# mcu_v052.net
KiCad netlist of a schematic drawn in EAGLE
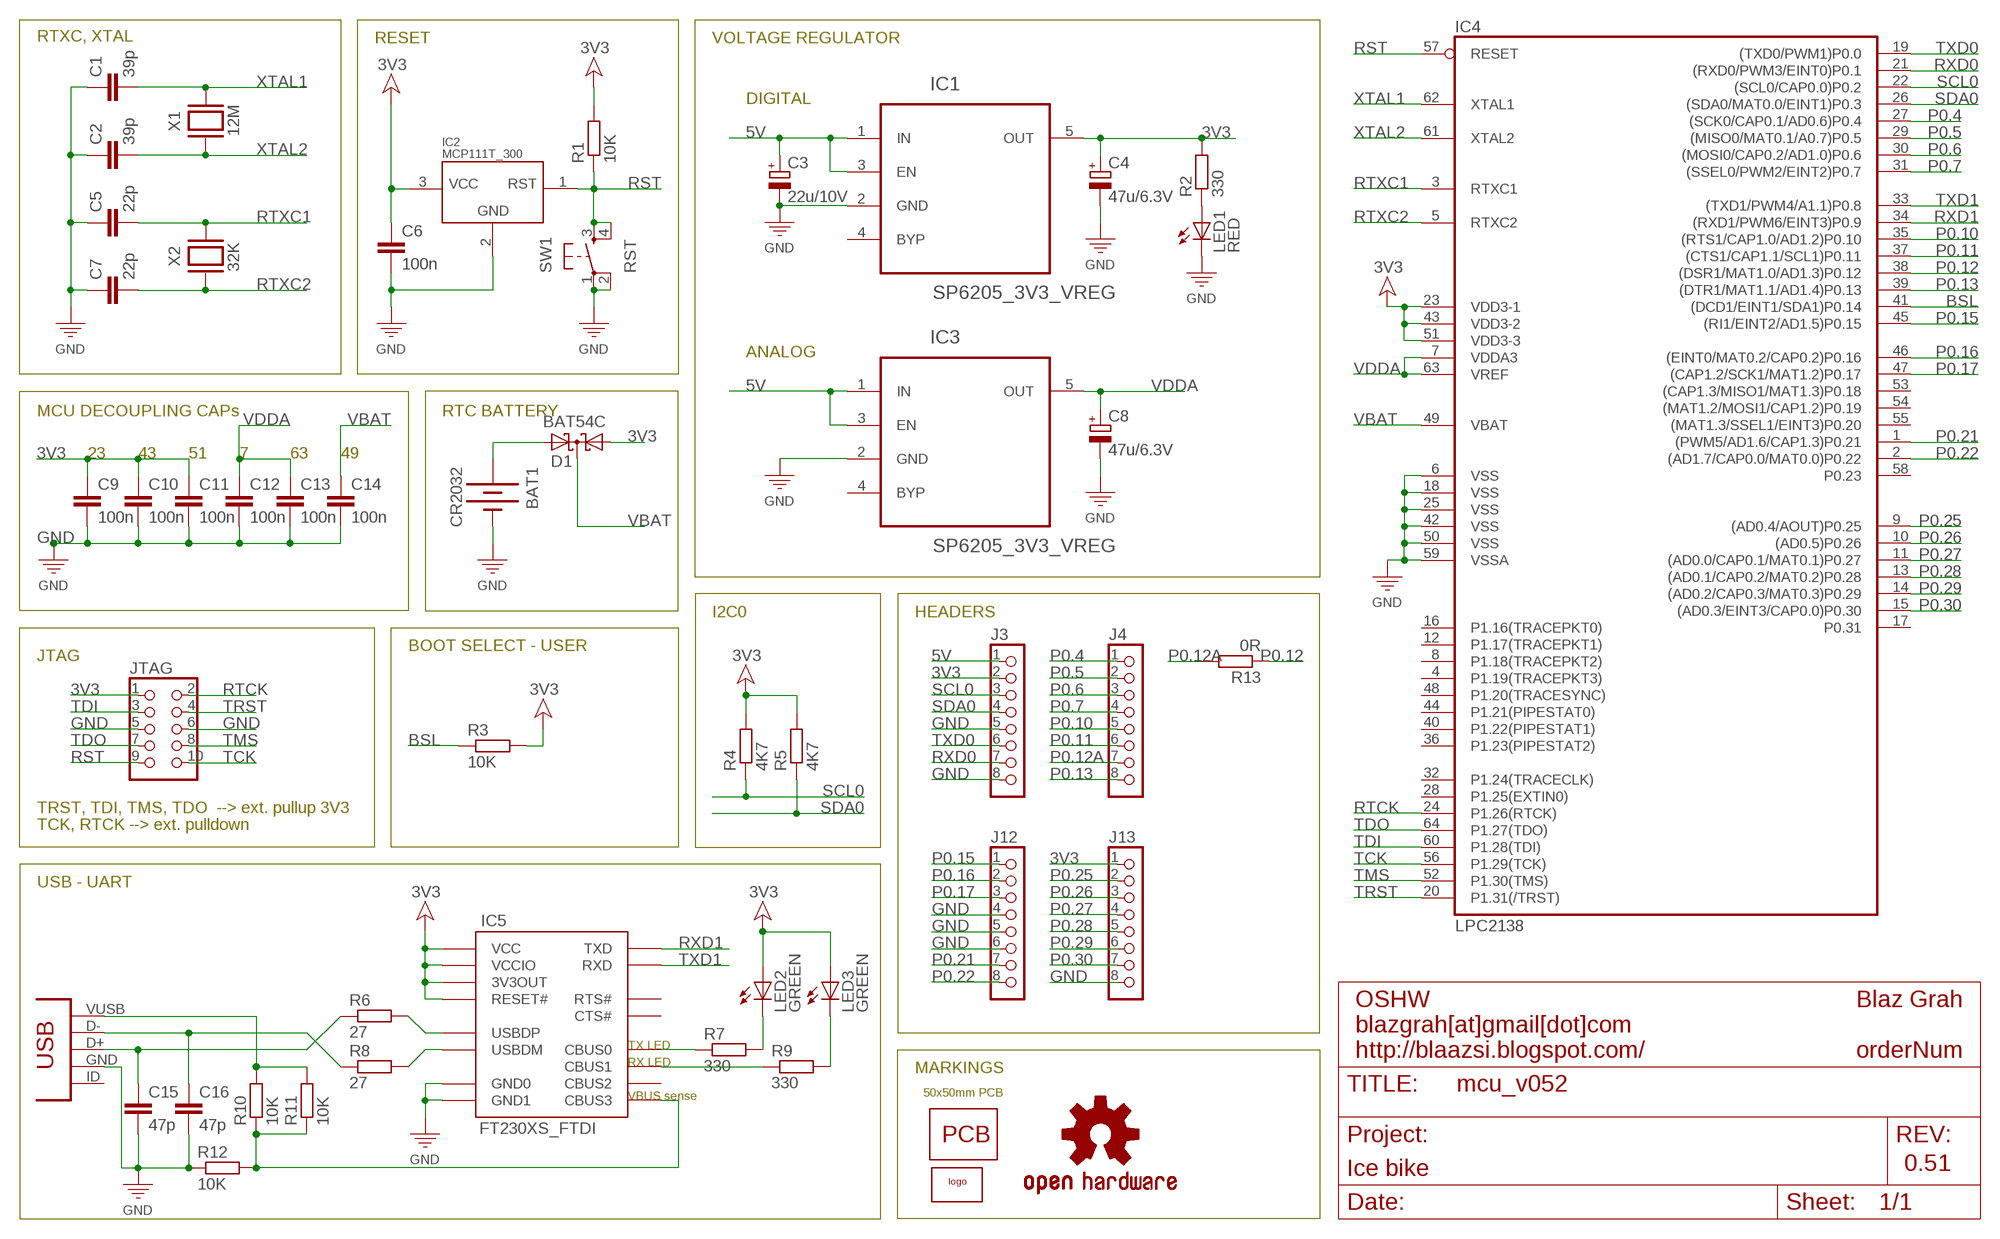
[diagram p0: schematic, sheet 1]

(export (version "E")
  (design (tool "Eeschema 10.0.6"))
  (components
    (comp (ref "BAT1")
      (value "CR2032")
      (footprint "eagle-import:BATTERY_20MM_SMD")
      (libsource (lib "eagle-import") (part "BATTERY20MM"))
    )
    (comp (ref "C1")
      (value "39p")
      (footprint "eagle-import:C0603")
      (libsource (lib "eagle-import") (part "C-EUC0603"))
    )
    (comp (ref "C2")
      (value "39p")
      (footprint "eagle-import:C0603")
      (libsource (lib "eagle-import") (part "C-EUC0603"))
    )
    (comp (ref "C3")
      (value "22u/10V")
      (footprint "eagle-import:SMC_B")
      (libsource (lib "eagle-import") (part "CAPACITOR_POL-SMC_B"))
    )
    (comp (ref "C4")
      (value "47u/6.3V")
      (footprint "eagle-import:SMC_B")
      (libsource (lib "eagle-import") (part "CAPACITOR_POL-SMC_B"))
    )
    (comp (ref "C5")
      (value "22p")
      (footprint "eagle-import:C0603")
      (libsource (lib "eagle-import") (part "C-EUC0603"))
    )
    (comp (ref "C6")
      (value "100n")
      (footprint "eagle-import:C0603")
      (libsource (lib "eagle-import") (part "C-EUC0603"))
    )
    (comp (ref "C7")
      (value "22p")
      (footprint "eagle-import:C0603")
      (libsource (lib "eagle-import") (part "C-EUC0603"))
    )
    (comp (ref "C8")
      (value "47u/6.3V")
      (footprint "eagle-import:SMC_B")
      (libsource (lib "eagle-import") (part "CAPACITOR_POL-SMC_B"))
    )
    (comp (ref "C9")
      (value "100n")
      (footprint "eagle-import:C0603")
      (libsource (lib "eagle-import") (part "C-EUC0603"))
    )
    (comp (ref "C10")
      (value "100n")
      (footprint "eagle-import:C0603")
      (libsource (lib "eagle-import") (part "C-EUC0603"))
    )
    (comp (ref "C11")
      (value "100n")
      (footprint "eagle-import:C0603")
      (libsource (lib "eagle-import") (part "C-EUC0603"))
    )
    (comp (ref "C12")
      (value "100n")
      (footprint "eagle-import:C0603")
      (libsource (lib "eagle-import") (part "C-EUC0603"))
    )
    (comp (ref "C13")
      (value "100n")
      (footprint "eagle-import:C0603")
      (libsource (lib "eagle-import") (part "C-EUC0603"))
    )
    (comp (ref "C14")
      (value "100n")
      (footprint "eagle-import:C0603")
      (libsource (lib "eagle-import") (part "C-EUC0603"))
    )
    (comp (ref "C15")
      (value "47p")
      (footprint "eagle-import:C0603")
      (libsource (lib "eagle-import") (part "C-EUC0603"))
    )
    (comp (ref "C16")
      (value "47p")
      (footprint "eagle-import:C0603")
      (libsource (lib "eagle-import") (part "C-EUC0603"))
    )
    (comp (ref "D1")
      (value "BAT54C")
      (footprint "eagle-import:SOT23")
      (libsource (lib "eagle-import") (part "BAT54C"))
    )
    (comp (ref "DOC")
      (value "FRAME_DINA4_L")
      (footprint "eagle-import:DP_LOGO")
      (fields
        (field (name "AUTHOR") "Blaz Grah")
        (field (name "DATE") "23.4.2012")
        (field (name "LICENSE") "OSHW")
        (field (name "PROJECT") "Ice bike")
        (field (name "REV") "0.51")
        (field (name "URL1") "blazgrah[at]gmail[dot]com")
        (field (name "URL2") "http://blaazsi.blogspot.com/")
      )
      (libsource (lib "eagle-import") (part "FRAME_DINA4_L"))
    )
    (comp (ref "IC1")
      (value "SP6205_3V3_VREG")
      (footprint "eagle-import:SOT23-5")
      (libsource (lib "eagle-import") (part "SP6205_3V3_VREG"))
    )
    (comp (ref "IC2")
      (value "MCP111T_300")
      (footprint "eagle-import:SOT23")
      (libsource (lib "eagle-import") (part "MCP111T_300"))
    )
    (comp (ref "IC3")
      (value "SP6205_3V3_VREG")
      (footprint "eagle-import:SOT23-5")
      (libsource (lib "eagle-import") (part "SP6205_3V3_VREG"))
    )
    (comp (ref "IC4")
      (value "LPC2138")
      (footprint "eagle-import:LQFP64")
      (libsource (lib "eagle-import") (part "LCP2138_LQFP64"))
    )
    (comp (ref "IC5")
      (value "FT230XS_FTDI")
      (footprint "eagle-import:SSOP16")
      (libsource (lib "eagle-import") (part "FT230XS_FTDI"))
    )
    (comp (ref "J3")
      (value "CON_HEADER_1X08-PTH")
      (footprint "eagle-import:M1X8")
      (libsource (lib "eagle-import") (part "CON_HEADER_1X08-PTH"))
    )
    (comp (ref "J4")
      (value "CON_HEADER_1X08-PTH")
      (footprint "eagle-import:M1X8")
      (libsource (lib "eagle-import") (part "CON_HEADER_1X08-PTH"))
    )
    (comp (ref "J12")
      (value "CON_HEADER_1X08-PTH")
      (footprint "eagle-import:M1X8")
      (libsource (lib "eagle-import") (part "CON_HEADER_1X08-PTH"))
    )
    (comp (ref "J13")
      (value "CON_HEADER_1X08-PTH")
      (footprint "eagle-import:M1X8")
      (libsource (lib "eagle-import") (part "CON_HEADER_1X08-PTH"))
    )
    (comp (ref "JTAG")
      (value "CON_HEADER_2X05-PTH+SHROUDED_A")
      (footprint "eagle-import:PINSHRD_PTH_2X05")
      (libsource (lib "eagle-import") (part "CON_HEADER_2X05-PTH+SHROUDED_A"))
    )
    (comp (ref "LED1")
      (value "RED")
      (footprint "eagle-import:LED0805")
      (libsource (lib "eagle-import") (part "LED0805"))
    )
    (comp (ref "LED2")
      (value "GREEN")
      (footprint "eagle-import:LED0805")
      (libsource (lib "eagle-import") (part "LED0805"))
    )
    (comp (ref "LED3")
      (value "GREEN")
      (footprint "eagle-import:LED0805")
      (libsource (lib "eagle-import") (part "LED0805"))
    )
    (comp (ref "LOGO1")
      (value "OSHW-LOGOS")
      (footprint "eagle-import:OSHW-LOGO-S")
      (libsource (lib "eagle-import") (part "OSHW-LOGOS"))
    )
    (comp (ref "PCB1")
      (value "PCB")
      (footprint "eagle-import:PCB_50X50")
      (libsource (lib "eagle-import") (part "PCB"))
    )
    (comp (ref "R1")
      (value "10K")
      (footprint "eagle-import:R0603")
      (libsource (lib "eagle-import") (part "R-EU0603"))
    )
    (comp (ref "R2")
      (value "330")
      (footprint "eagle-import:R0603")
      (libsource (lib "eagle-import") (part "R-EU0603"))
    )
    (comp (ref "R3")
      (value "10K")
      (footprint "eagle-import:R0603")
      (libsource (lib "eagle-import") (part "R-EU0603"))
    )
    (comp (ref "R4")
      (value "4K7")
      (footprint "eagle-import:R0603")
      (libsource (lib "eagle-import") (part "R-EU0603"))
    )
    (comp (ref "R5")
      (value "4K7")
      (footprint "eagle-import:R0603")
      (libsource (lib "eagle-import") (part "R-EU0603"))
    )
    (comp (ref "R6")
      (value "27")
      (footprint "eagle-import:R0603")
      (libsource (lib "eagle-import") (part "R-EU0603"))
    )
    (comp (ref "R7")
      (value "330")
      (footprint "eagle-import:R0603")
      (libsource (lib "eagle-import") (part "R-EU0603"))
    )
    (comp (ref "R8")
      (value "27")
      (footprint "eagle-import:R0603")
      (libsource (lib "eagle-import") (part "R-EU0603"))
    )
    (comp (ref "R9")
      (value "330")
      (footprint "eagle-import:R0603")
      (libsource (lib "eagle-import") (part "R-EU0603"))
    )
    (comp (ref "R10")
      (value "10K")
      (footprint "eagle-import:R0603")
      (libsource (lib "eagle-import") (part "R-EU0603"))
    )
    (comp (ref "R11")
      (value "10K")
      (footprint "eagle-import:R0603")
      (libsource (lib "eagle-import") (part "R-EU0603"))
    )
    (comp (ref "R12")
      (value "10K")
      (footprint "eagle-import:R0603")
      (libsource (lib "eagle-import") (part "R-EU0603"))
    )
    (comp (ref "R13")
      (value "0R")
      (footprint "eagle-import:R0603_JUMP")
      (libsource (lib "eagle-import") (part "R-EU0603J"))
    )
    (comp (ref "SW1")
      (value "RST")
      (footprint "eagle-import:BUTTON_SW_4P_SMD")
      (libsource (lib "eagle-import") (part "TACTIL_BUTTON"))
    )
    (comp (ref "U$13")
      (value "LOGO")
      (footprint "eagle-import:LOGO_SMILE")
      (libsource (lib "eagle-import") (part "LOGO"))
    )
    (comp (ref "USB1")
      (value "CON-USB-F-MINI-B")
      (footprint "eagle-import:CONN_USB_MINI-B")
      (libsource (lib "eagle-import") (part "CON-USB-F-MINI-B"))
    )
    (comp (ref "X1")
      (value "12M")
      (footprint "eagle-import:CRYSTAL_12M_4.8X10.6MM")
      (libsource (lib "eagle-import") (part "CRYSTALSMD_4.8X10.6"))
    )
    (comp (ref "X2")
      (value "32K")
      (footprint "eagle-import:CRYSTAL_32K_SMD")
      (libsource (lib "eagle-import") (part "CRYSTALSMD_32K"))
    )
  )
  (nets
    (net (code "1") (name "/5V") (class "Default")
      (node (ref "C3") (pin "+") (pinfunction "+_+") (pintype "passive"))
      (node (ref "IC1") (pin "1") (pinfunction "IN_1") (pintype "input"))
      (node (ref "IC1") (pin "3") (pinfunction "EN_3") (pintype "input"))
      (node (ref "IC3") (pin "1") (pinfunction "IN_1") (pintype "input"))
      (node (ref "IC3") (pin "3") (pinfunction "EN_3") (pintype "input"))
      (node (ref "J3") (pin "1") (pinfunction "1_1") (pintype "passive"))
    )
    (net (code "2") (name "/BSL") (class "Default")
      (node (ref "IC4") (pin "41") (pinfunction "(DCD1/EINT1/SDA1)P0.14_41") (pintype "bidirectional"))
      (node (ref "R3") (pin "1") (pinfunction "1_1") (pintype "passive"))
    )
    (net (code "3") (name "/P0.4") (class "Default")
      (node (ref "IC4") (pin "27") (pinfunction "(SCK0/CAP0.1/AD0.6)P0.4_27") (pintype "bidirectional"))
      (node (ref "J4") (pin "1") (pinfunction "1_1") (pintype "passive"))
    )
    (net (code "4") (name "/P0.5") (class "Default")
      (node (ref "IC4") (pin "29") (pinfunction "(MISO0/MAT0.1/A0.7)P0.5_29") (pintype "bidirectional"))
      (node (ref "J4") (pin "2") (pinfunction "2_2") (pintype "passive"))
    )
    (net (code "5") (name "/P0.6") (class "Default")
      (node (ref "IC4") (pin "30") (pinfunction "(MOSI0/CAP0.2/AD1.0)P0.6_30") (pintype "bidirectional"))
      (node (ref "J4") (pin "3") (pinfunction "3_3") (pintype "passive"))
    )
    (net (code "6") (name "/P0.7") (class "Default")
      (node (ref "IC4") (pin "31") (pinfunction "(SSEL0/PWM2/EINT2)P0.7_31") (pintype "bidirectional"))
      (node (ref "J4") (pin "4") (pinfunction "4_4") (pintype "passive"))
    )
    (net (code "7") (name "/P0.10") (class "Default")
      (node (ref "IC4") (pin "35") (pinfunction "(RTS1/CAP1.0/AD1.2)P0.10_35") (pintype "bidirectional"))
      (node (ref "J4") (pin "5") (pinfunction "5_5") (pintype "passive"))
    )
    (net (code "8") (name "/P0.11") (class "Default")
      (node (ref "IC4") (pin "37") (pinfunction "(CTS1/CAP1.1/SCL1)P0.11_37") (pintype "bidirectional"))
      (node (ref "J4") (pin "6") (pinfunction "6_6") (pintype "passive"))
    )
    (net (code "9") (name "/P0.12") (class "Default")
      (node (ref "IC4") (pin "38") (pinfunction "(DSR1/MAT1.0/AD1.3)P0.12_38") (pintype "bidirectional"))
      (node (ref "R13") (pin "1") (pinfunction "1_1") (pintype "passive"))
    )
    (net (code "10") (name "/P0.12A") (class "Default")
      (node (ref "J4") (pin "7") (pinfunction "7_7") (pintype "passive"))
      (node (ref "R13") (pin "2") (pinfunction "2_2") (pintype "passive"))
    )
    (net (code "11") (name "/P0.13") (class "Default")
      (node (ref "IC4") (pin "39") (pinfunction "(DTR1/MAT1.1/AD1.4)P0.13_39") (pintype "bidirectional"))
      (node (ref "J4") (pin "8") (pinfunction "8_8") (pintype "passive"))
    )
    (net (code "12") (name "/P0.15") (class "Default")
      (node (ref "IC4") (pin "45") (pinfunction "(RI1/EINT2/AD1.5)P0.15_45") (pintype "bidirectional"))
      (node (ref "J12") (pin "1") (pinfunction "1_1") (pintype "passive"))
    )
    (net (code "13") (name "/P0.16") (class "Default")
      (node (ref "IC4") (pin "46") (pinfunction "(EINT0/MAT0.2/CAP0.2)P0.16_46") (pintype "bidirectional"))
      (node (ref "J12") (pin "2") (pinfunction "2_2") (pintype "passive"))
    )
    (net (code "14") (name "/P0.17") (class "Default")
      (node (ref "IC4") (pin "47") (pinfunction "(CAP1.2/SCK1/MAT1.2)P0.17_47") (pintype "bidirectional"))
      (node (ref "J12") (pin "3") (pinfunction "3_3") (pintype "passive"))
    )
    (net (code "15") (name "/P0.21") (class "Default")
      (node (ref "IC4") (pin "1") (pinfunction "(PWM5/AD1.6/CAP1.3)P0.21_1") (pintype "bidirectional"))
      (node (ref "J12") (pin "7") (pinfunction "7_7") (pintype "passive"))
    )
    (net (code "16") (name "/P0.22") (class "Default")
      (node (ref "IC4") (pin "2") (pinfunction "(AD1.7/CAP0.0/MAT0.0)P0.22_2") (pintype "bidirectional"))
      (node (ref "J12") (pin "8") (pinfunction "8_8") (pintype "passive"))
    )
    (net (code "17") (name "/P0.25") (class "Default")
      (node (ref "IC4") (pin "9") (pinfunction "(AD0.4/AOUT)P0.25_9") (pintype "bidirectional"))
      (node (ref "J13") (pin "2") (pinfunction "2_2") (pintype "passive"))
    )
    (net (code "18") (name "/P0.26") (class "Default")
      (node (ref "IC4") (pin "10") (pinfunction "(AD0.5)P0.26_10") (pintype "bidirectional"))
      (node (ref "J13") (pin "3") (pinfunction "3_3") (pintype "passive"))
    )
    (net (code "19") (name "/P0.27") (class "Default")
      (node (ref "IC4") (pin "11") (pinfunction "(AD0.0/CAP0.1/MAT0.1)P0.27_11") (pintype "bidirectional"))
      (node (ref "J13") (pin "4") (pinfunction "4_4") (pintype "passive"))
    )
    (net (code "20") (name "/P0.28") (class "Default")
      (node (ref "IC4") (pin "13") (pinfunction "(AD0.1/CAP0.2/MAT0.2)P0.28_13") (pintype "bidirectional"))
      (node (ref "J13") (pin "5") (pinfunction "5_5") (pintype "passive"))
    )
    (net (code "21") (name "/P0.29") (class "Default")
      (node (ref "IC4") (pin "14") (pinfunction "(AD0.2/CAP0.3/MAT0.3)P0.29_14") (pintype "bidirectional"))
      (node (ref "J13") (pin "6") (pinfunction "6_6") (pintype "passive"))
    )
    (net (code "22") (name "/P0.30") (class "Default")
      (node (ref "IC4") (pin "15") (pinfunction "(AD0.3/EINT3/CAP0.0)P0.30_15") (pintype "bidirectional"))
      (node (ref "J13") (pin "7") (pinfunction "7_7") (pintype "passive"))
    )
    (net (code "23") (name "/RST") (class "Default")
      (node (ref "IC2") (pin "1") (pinfunction "RST_1") (pintype "output"))
      (node (ref "IC4") (pin "57") (pinfunction "RESET_57") (pintype "input"))
      (node (ref "JTAG") (pin "9") (pinfunction "9_9") (pintype "passive"))
      (node (ref "R1") (pin "1") (pinfunction "1_1") (pintype "passive"))
      (node (ref "SW1") (pin "3") (pinfunction "3_3") (pintype "passive"))
      (node (ref "SW1") (pin "4") (pinfunction "4_4") (pintype "passive"))
    )
    (net (code "24") (name "/RTCK") (class "Default")
      (node (ref "IC4") (pin "24") (pinfunction "P1.26(RTCK)_24") (pintype "bidirectional"))
      (node (ref "JTAG") (pin "2") (pinfunction "2_2") (pintype "passive"))
    )
    (net (code "25") (name "/RTXC1") (class "Default")
      (node (ref "C5") (pin "2") (pinfunction "2_2") (pintype "passive"))
      (node (ref "IC4") (pin "3") (pinfunction "RTXC1_3") (pintype "input"))
      (node (ref "X2") (pin "X2") (pinfunction "2_X2") (pintype "passive"))
    )
    (net (code "26") (name "/RTXC2") (class "Default")
      (node (ref "C7") (pin "2") (pinfunction "2_2") (pintype "passive"))
      (node (ref "IC4") (pin "5") (pinfunction "RTXC2_5") (pintype "output"))
      (node (ref "X2") (pin "X1") (pinfunction "1_X1") (pintype "passive"))
    )
    (net (code "27") (name "/RXD0") (class "Default")
      (node (ref "IC4") (pin "21") (pinfunction "(RXD0/PWM3/EINT0)P0.1_21") (pintype "bidirectional"))
      (node (ref "J3") (pin "7") (pinfunction "7_7") (pintype "passive"))
    )
    (net (code "28") (name "/RXD1") (class "Default")
      (node (ref "IC4") (pin "34") (pinfunction "(RXD1/PWM6/EINT3)P0.9_34") (pintype "bidirectional"))
      (node (ref "IC5") (pin "P$1") (pinfunction "TXD_P$1") (pintype "bidirectional"))
    )
    (net (code "29") (name "/SCL0") (class "Default")
      (node (ref "IC4") (pin "22") (pinfunction "(SCL0/CAP0.0)P0.2_22") (pintype "bidirectional"))
      (node (ref "J3") (pin "3") (pinfunction "3_3") (pintype "passive"))
      (node (ref "R4") (pin "1") (pinfunction "1_1") (pintype "passive"))
    )
    (net (code "30") (name "/SDA0") (class "Default")
      (node (ref "IC4") (pin "26") (pinfunction "(SDA0/MAT0.0/EINT1)P0.3_26") (pintype "bidirectional"))
      (node (ref "J3") (pin "4") (pinfunction "4_4") (pintype "passive"))
      (node (ref "R5") (pin "1") (pinfunction "1_1") (pintype "passive"))
    )
    (net (code "31") (name "/TCK") (class "Default")
      (node (ref "IC4") (pin "56") (pinfunction "P1.29(TCK)_56") (pintype "bidirectional"))
      (node (ref "JTAG") (pin "10") (pinfunction "10_10") (pintype "passive"))
    )
    (net (code "32") (name "/TDI") (class "Default")
      (node (ref "IC4") (pin "60") (pinfunction "P1.28(TDI)_60") (pintype "bidirectional"))
      (node (ref "JTAG") (pin "3") (pinfunction "3_3") (pintype "passive"))
    )
    (net (code "33") (name "/TDO") (class "Default")
      (node (ref "IC4") (pin "64") (pinfunction "P1.27(TDO)_64") (pintype "bidirectional"))
      (node (ref "JTAG") (pin "7") (pinfunction "7_7") (pintype "passive"))
    )
    (net (code "34") (name "/TMS") (class "Default")
      (node (ref "IC4") (pin "52") (pinfunction "P1.30(TMS)_52") (pintype "bidirectional"))
      (node (ref "JTAG") (pin "8") (pinfunction "8_8") (pintype "passive"))
    )
    (net (code "35") (name "/TRST") (class "Default")
      (node (ref "IC4") (pin "20") (pinfunction "P1.31(/TRST)_20") (pintype "bidirectional"))
      (node (ref "JTAG") (pin "4") (pinfunction "4_4") (pintype "passive"))
    )
    (net (code "36") (name "/TXD0") (class "Default")
      (node (ref "IC4") (pin "19") (pinfunction "(TXD0/PWM1)P0.0_19") (pintype "bidirectional"))
      (node (ref "J3") (pin "6") (pinfunction "6_6") (pintype "passive"))
    )
    (net (code "37") (name "/TXD1") (class "Default")
      (node (ref "IC4") (pin "33") (pinfunction "(TXD1/PWM4/A1.1)P0.8_33") (pintype "bidirectional"))
      (node (ref "IC5") (pin "P$4") (pinfunction "RXD_P$4") (pintype "bidirectional"))
    )
    (net (code "38") (name "/VBAT") (class "Default")
      (node (ref "C14") (pin "1") (pinfunction "1_1") (pintype "passive"))
      (node (ref "D1") (pin "3") (pinfunction "CC_3") (pintype "passive"))
      (node (ref "IC4") (pin "49") (pinfunction "VBAT_49") (pintype "power_in"))
    )
    (net (code "39") (name "/VDDA") (class "Default")
      (node (ref "C12") (pin "1") (pinfunction "1_1") (pintype "passive"))
      (node (ref "C13") (pin "1") (pinfunction "1_1") (pintype "passive"))
      (node (ref "C8") (pin "+") (pinfunction "+_+") (pintype "passive"))
      (node (ref "IC3") (pin "5") (pinfunction "OUT_5") (pintype "power_in"))
      (node (ref "IC4") (pin "63") (pinfunction "VREF_63") (pintype "input"))
      (node (ref "IC4") (pin "7") (pinfunction "VDDA3_7") (pintype "power_in"))
    )
    (net (code "40") (name "/XTAL1") (class "Default")
      (node (ref "C1") (pin "2") (pinfunction "2_2") (pintype "passive"))
      (node (ref "IC4") (pin "62") (pinfunction "XTAL1_62") (pintype "input"))
      (node (ref "X1") (pin "P$2") (pinfunction "2_P$2") (pintype "passive"))
    )
    (net (code "41") (name "/XTAL2") (class "Default")
      (node (ref "C2") (pin "2") (pinfunction "2_2") (pintype "passive"))
      (node (ref "IC4") (pin "61") (pinfunction "XTAL2_61") (pintype "output"))
      (node (ref "X1") (pin "P$1") (pinfunction "1_P$1") (pintype "passive"))
    )
    (net (code "42") (name "3V3") (class "Default")
      (node (ref "C10") (pin "1") (pinfunction "1_1") (pintype "passive"))
      (node (ref "C11") (pin "1") (pinfunction "1_1") (pintype "passive"))
      (node (ref "C4") (pin "+") (pinfunction "+_+") (pintype "passive"))
      (node (ref "C6") (pin "1") (pinfunction "1_1") (pintype "passive"))
      (node (ref "C9") (pin "1") (pinfunction "1_1") (pintype "passive"))
      (node (ref "D1") (pin "1") (pinfunction "A1_1") (pintype "passive"))
      (node (ref "IC1") (pin "5") (pinfunction "OUT_5") (pintype "power_in"))
      (node (ref "IC2") (pin "3") (pinfunction "VCC_3") (pintype "input"))
      (node (ref "IC4") (pin "23") (pinfunction "VDD3-1_23") (pintype "power_in"))
      (node (ref "IC4") (pin "43") (pinfunction "VDD3-2_43") (pintype "power_in"))
      (node (ref "IC4") (pin "51") (pinfunction "VDD3-3_51") (pintype "power_in"))
      (node (ref "IC5") (pin "P$10") (pinfunction "3V3OUT_P$10") (pintype "power_in"))
      (node (ref "IC5") (pin "P$11") (pinfunction "RESET#_P$11") (pintype "bidirectional"))
      (node (ref "IC5") (pin "P$12") (pinfunction "VCC_P$12") (pintype "power_in"))
      (node (ref "IC5") (pin "P$3") (pinfunction "VCCIO_P$3") (pintype "power_in"))
      (node (ref "J13") (pin "1") (pinfunction "1_1") (pintype "passive"))
      (node (ref "J3") (pin "2") (pinfunction "2_2") (pintype "passive"))
      (node (ref "JTAG") (pin "1") (pinfunction "1_1") (pintype "passive"))
      (node (ref "LED2") (pin "A") (pinfunction "A_A") (pintype "passive"))
      (node (ref "LED3") (pin "A") (pinfunction "A_A") (pintype "passive"))
      (node (ref "R1") (pin "2") (pinfunction "2_2") (pintype "passive"))
      (node (ref "R2") (pin "2") (pinfunction "2_2") (pintype "passive"))
      (node (ref "R3") (pin "2") (pinfunction "2_2") (pintype "passive"))
      (node (ref "R4") (pin "2") (pinfunction "2_2") (pintype "passive"))
      (node (ref "R5") (pin "2") (pinfunction "2_2") (pintype "passive"))
    )
    (net (code "43") (name "GND") (class "Default")
      (node (ref "BAT1") (pin "NEG") (pinfunction "NEG_NEG") (pintype "power_in"))
      (node (ref "C1") (pin "1") (pinfunction "1_1") (pintype "passive"))
      (node (ref "C10") (pin "2") (pinfunction "2_2") (pintype "passive"))
      (node (ref "C11") (pin "2") (pinfunction "2_2") (pintype "passive"))
      (node (ref "C12") (pin "2") (pinfunction "2_2") (pintype "passive"))
      (node (ref "C13") (pin "2") (pinfunction "2_2") (pintype "passive"))
      (node (ref "C14") (pin "2") (pinfunction "2_2") (pintype "passive"))
      (node (ref "C15") (pin "2") (pinfunction "2_2") (pintype "passive"))
      (node (ref "C16") (pin "2") (pinfunction "2_2") (pintype "passive"))
      (node (ref "C2") (pin "1") (pinfunction "1_1") (pintype "passive"))
      (node (ref "C3") (pin "-") (pinfunction "-_-") (pintype "passive"))
      (node (ref "C4") (pin "-") (pinfunction "-_-") (pintype "passive"))
      (node (ref "C5") (pin "1") (pinfunction "1_1") (pintype "passive"))
      (node (ref "C6") (pin "2") (pinfunction "2_2") (pintype "passive"))
      (node (ref "C7") (pin "1") (pinfunction "1_1") (pintype "passive"))
      (node (ref "C8") (pin "-") (pinfunction "-_-") (pintype "passive"))
      (node (ref "C9") (pin "2") (pinfunction "2_2") (pintype "passive"))
      (node (ref "IC1") (pin "2") (pinfunction "GND_2") (pintype "power_in"))
      (node (ref "IC2") (pin "2") (pinfunction "GND_2") (pintype "power_in"))
      (node (ref "IC3") (pin "2") (pinfunction "GND_2") (pintype "power_in"))
      (node (ref "IC4") (pin "18") (pinfunction "VSS_18") (pintype "power_in"))
      (node (ref "IC4") (pin "25") (pinfunction "VSS_25") (pintype "power_in"))
      (node (ref "IC4") (pin "42") (pinfunction "VSS_42") (pintype "power_in"))
      (node (ref "IC4") (pin "50") (pinfunction "VSS_50") (pintype "power_in"))
      (node (ref "IC4") (pin "59") (pinfunction "VSSA_59") (pintype "power_in"))
      (node (ref "IC4") (pin "6") (pinfunction "VSS_6") (pintype "power_in"))
      (node (ref "IC5") (pin "P$13") (pinfunction "GND1_P$13") (pintype "power_in"))
      (node (ref "IC5") (pin "P$5") (pinfunction "GND0_P$5") (pintype "power_in"))
      (node (ref "J12") (pin "4") (pinfunction "4_4") (pintype "passive"))
      (node (ref "J12") (pin "5") (pinfunction "5_5") (pintype "passive"))
      (node (ref "J12") (pin "6") (pinfunction "6_6") (pintype "passive"))
      (node (ref "J13") (pin "8") (pinfunction "8_8") (pintype "passive"))
      (node (ref "J3") (pin "5") (pinfunction "5_5") (pintype "passive"))
      (node (ref "J3") (pin "8") (pinfunction "8_8") (pintype "passive"))
      (node (ref "JTAG") (pin "5") (pinfunction "5_5") (pintype "passive"))
      (node (ref "JTAG") (pin "6") (pinfunction "6_6") (pintype "passive"))
      (node (ref "LED1") (pin "C") (pinfunction "C_C") (pintype "passive"))
      (node (ref "R12") (pin "1") (pinfunction "1_1") (pintype "passive"))
      (node (ref "SW1") (pin "1") (pinfunction "1_1") (pintype "passive"))
      (node (ref "SW1") (pin "2") (pinfunction "2_2") (pintype "passive"))
      (node (ref "USB1") (pin "GND") (pinfunction "GND_GND") (pintype "bidirectional"))
    )
    (net (code "44") (name "Net-(C15-Pad1)") (class "Default")
      (node (ref "C15") (pin "1") (pinfunction "1_1") (pintype "passive"))
      (node (ref "R6") (pin "1") (pinfunction "1_1") (pintype "passive"))
      (node (ref "USB1") (pin "D+") (pinfunction "D+_D+") (pintype "bidirectional"))
    )
    (net (code "45") (name "Net-(C16-Pad1)") (class "Default")
      (node (ref "C16") (pin "1") (pinfunction "1_1") (pintype "passive"))
      (node (ref "R8") (pin "1") (pinfunction "1_1") (pintype "passive"))
      (node (ref "USB1") (pin "D-") (pinfunction "D-_D-") (pintype "bidirectional"))
    )
    (net (code "46") (name "Net-(D1-A2)") (class "Default")
      (node (ref "BAT1") (pin "POS1") (pinfunction "POZ_POS1") (pintype "power_in"))
      (node (ref "BAT1") (pin "POS2") (pinfunction "POZ_POS2") (pintype "power_in"))
      (node (ref "D1") (pin "2") (pinfunction "A2_2") (pintype "passive"))
    )
    (net (code "47") (name "Net-(IC5-CBUS0)") (class "Default")
      (node (ref "IC5") (pin "P$15") (pinfunction "CBUS0_P$15") (pintype "bidirectional"))
      (node (ref "R7") (pin "1") (pinfunction "1_1") (pintype "passive"))
    )
    (net (code "48") (name "Net-(IC5-CBUS1)") (class "Default")
      (node (ref "IC5") (pin "P$14") (pinfunction "CBUS1_P$14") (pintype "bidirectional"))
      (node (ref "R9") (pin "1") (pinfunction "1_1") (pintype "passive"))
    )
    (net (code "49") (name "Net-(IC5-CBUS3)") (class "Default")
      (node (ref "IC5") (pin "P$16") (pinfunction "CBUS3_P$16") (pintype "bidirectional"))
      (node (ref "R10") (pin "1") (pinfunction "1_1") (pintype "passive"))
      (node (ref "R11") (pin "1") (pinfunction "1_1") (pintype "passive"))
      (node (ref "R12") (pin "2") (pinfunction "2_2") (pintype "passive"))
    )
    (net (code "50") (name "Net-(IC5-USBDM)") (class "Default")
      (node (ref "IC5") (pin "P$9") (pinfunction "USBDM_P$9") (pintype "bidirectional"))
      (node (ref "R8") (pin "2") (pinfunction "2_2") (pintype "passive"))
    )
    (net (code "51") (name "Net-(IC5-USBDP)") (class "Default")
      (node (ref "IC5") (pin "P$8") (pinfunction "USBDP_P$8") (pintype "bidirectional"))
      (node (ref "R6") (pin "2") (pinfunction "2_2") (pintype "passive"))
    )
    (net (code "52") (name "Net-(LED1-PadA)") (class "Default")
      (node (ref "LED1") (pin "A") (pinfunction "A_A") (pintype "passive"))
      (node (ref "R2") (pin "1") (pinfunction "1_1") (pintype "passive"))
    )
    (net (code "53") (name "Net-(LED2-PadC)") (class "Default")
      (node (ref "LED2") (pin "C") (pinfunction "C_C") (pintype "passive"))
      (node (ref "R7") (pin "2") (pinfunction "2_2") (pintype "passive"))
    )
    (net (code "54") (name "Net-(LED3-PadC)") (class "Default")
      (node (ref "LED3") (pin "C") (pinfunction "C_C") (pintype "passive"))
      (node (ref "R9") (pin "2") (pinfunction "2_2") (pintype "passive"))
    )
    (net (code "55") (name "Net-(R10-Pad2)") (class "Default")
      (node (ref "R10") (pin "2") (pinfunction "2_2") (pintype "passive"))
      (node (ref "R11") (pin "2") (pinfunction "2_2") (pintype "passive"))
      (node (ref "USB1") (pin "VUSB") (pinfunction "VUSB_VUSB") (pintype "bidirectional"))
    )
    (net (code "56") (name "unconnected-(IC1-BYP-Pad4)") (class "Default")
      (node (ref "IC1") (pin "4") (pinfunction "BYP_4") (pintype "no_connect"))
    )
    (net (code "57") (name "unconnected-(IC3-BYP-Pad4)") (class "Default")
      (node (ref "IC3") (pin "4") (pinfunction "BYP_4") (pintype "no_connect"))
    )
    (net (code "58") (name "unconnected-(IC4-(CAP1.3{slash}MISO1{slash}MAT1.3)P0.18-Pad53)") (class "Default")
      (node (ref "IC4") (pin "53") (pinfunction "(CAP1.3/MISO1/MAT1.3)P0.18_53") (pintype "bidirectional"))
    )
    (net (code "59") (name "unconnected-(IC4-(MAT1.2{slash}MOSI1{slash}CAP1.2)P0.19-Pad54)") (class "Default")
      (node (ref "IC4") (pin "54") (pinfunction "(MAT1.2/MOSI1/CAP1.2)P0.19_54") (pintype "bidirectional"))
    )
    (net (code "60") (name "unconnected-(IC4-(MAT1.3{slash}SSEL1{slash}EINT3)P0.20-Pad55)") (class "Default")
      (node (ref "IC4") (pin "55") (pinfunction "(MAT1.3/SSEL1/EINT3)P0.20_55") (pintype "bidirectional"))
    )
    (net (code "61") (name "unconnected-(IC4-P0.23-Pad58)") (class "Default")
      (node (ref "IC4") (pin "58") (pinfunction "P0.23_58") (pintype "bidirectional"))
    )
    (net (code "62") (name "unconnected-(IC4-P0.31-Pad17)") (class "Default")
      (node (ref "IC4") (pin "17") (pinfunction "P0.31_17") (pintype "output"))
    )
    (net (code "63") (name "unconnected-(IC4-P1.16(TRACEPKT0)-Pad16)") (class "Default")
      (node (ref "IC4") (pin "16") (pinfunction "P1.16(TRACEPKT0)_16") (pintype "bidirectional"))
    )
    (net (code "64") (name "unconnected-(IC4-P1.17(TRACEPKT1)-Pad12)") (class "Default")
      (node (ref "IC4") (pin "12") (pinfunction "P1.17(TRACEPKT1)_12") (pintype "bidirectional"))
    )
    (net (code "65") (name "unconnected-(IC4-P1.18(TRACEPKT2)-Pad8)") (class "Default")
      (node (ref "IC4") (pin "8") (pinfunction "P1.18(TRACEPKT2)_8") (pintype "bidirectional"))
    )
    (net (code "66") (name "unconnected-(IC4-P1.19(TRACEPKT3)-Pad4)") (class "Default")
      (node (ref "IC4") (pin "4") (pinfunction "P1.19(TRACEPKT3)_4") (pintype "bidirectional"))
    )
    (net (code "67") (name "unconnected-(IC4-P1.20(TRACESYNC)-Pad48)") (class "Default")
      (node (ref "IC4") (pin "48") (pinfunction "P1.20(TRACESYNC)_48") (pintype "bidirectional"))
    )
    (net (code "68") (name "unconnected-(IC4-P1.21(PIPESTAT0)-Pad44)") (class "Default")
      (node (ref "IC4") (pin "44") (pinfunction "P1.21(PIPESTAT0)_44") (pintype "bidirectional"))
    )
    (net (code "69") (name "unconnected-(IC4-P1.22(PIPESTAT1)-Pad40)") (class "Default")
      (node (ref "IC4") (pin "40") (pinfunction "P1.22(PIPESTAT1)_40") (pintype "bidirectional"))
    )
    (net (code "70") (name "unconnected-(IC4-P1.23(PIPESTAT2)-Pad36)") (class "Default")
      (node (ref "IC4") (pin "36") (pinfunction "P1.23(PIPESTAT2)_36") (pintype "bidirectional"))
    )
    (net (code "71") (name "unconnected-(IC4-P1.24(TRACECLK)-Pad32)") (class "Default")
      (node (ref "IC4") (pin "32") (pinfunction "P1.24(TRACECLK)_32") (pintype "bidirectional"))
    )
    (net (code "72") (name "unconnected-(IC4-P1.25(EXTIN0)-Pad28)") (class "Default")
      (node (ref "IC4") (pin "28") (pinfunction "P1.25(EXTIN0)_28") (pintype "bidirectional"))
    )
    (net (code "73") (name "unconnected-(IC5-CBUS2-PadP$7)") (class "Default")
      (node (ref "IC5") (pin "P$7") (pinfunction "CBUS2_P$7") (pintype "bidirectional"))
    )
    (net (code "74") (name "unconnected-(IC5-CTS#-PadP$6)") (class "Default")
      (node (ref "IC5") (pin "P$6") (pinfunction "CTS#_P$6") (pintype "bidirectional"))
    )
    (net (code "75") (name "unconnected-(IC5-RTS#-PadP$2)") (class "Default")
      (node (ref "IC5") (pin "P$2") (pinfunction "RTS#_P$2") (pintype "bidirectional"))
    )
    (net (code "76") (name "unconnected-(USB1B-USBID-PadID)") (class "Default")
      (node (ref "USB1") (pin "ID") (pinfunction "USBID_ID") (pintype "bidirectional"))
    )
  )
)
